# MedusaTester.net
KiCad netlist of a schematic drawn in Altium Designer
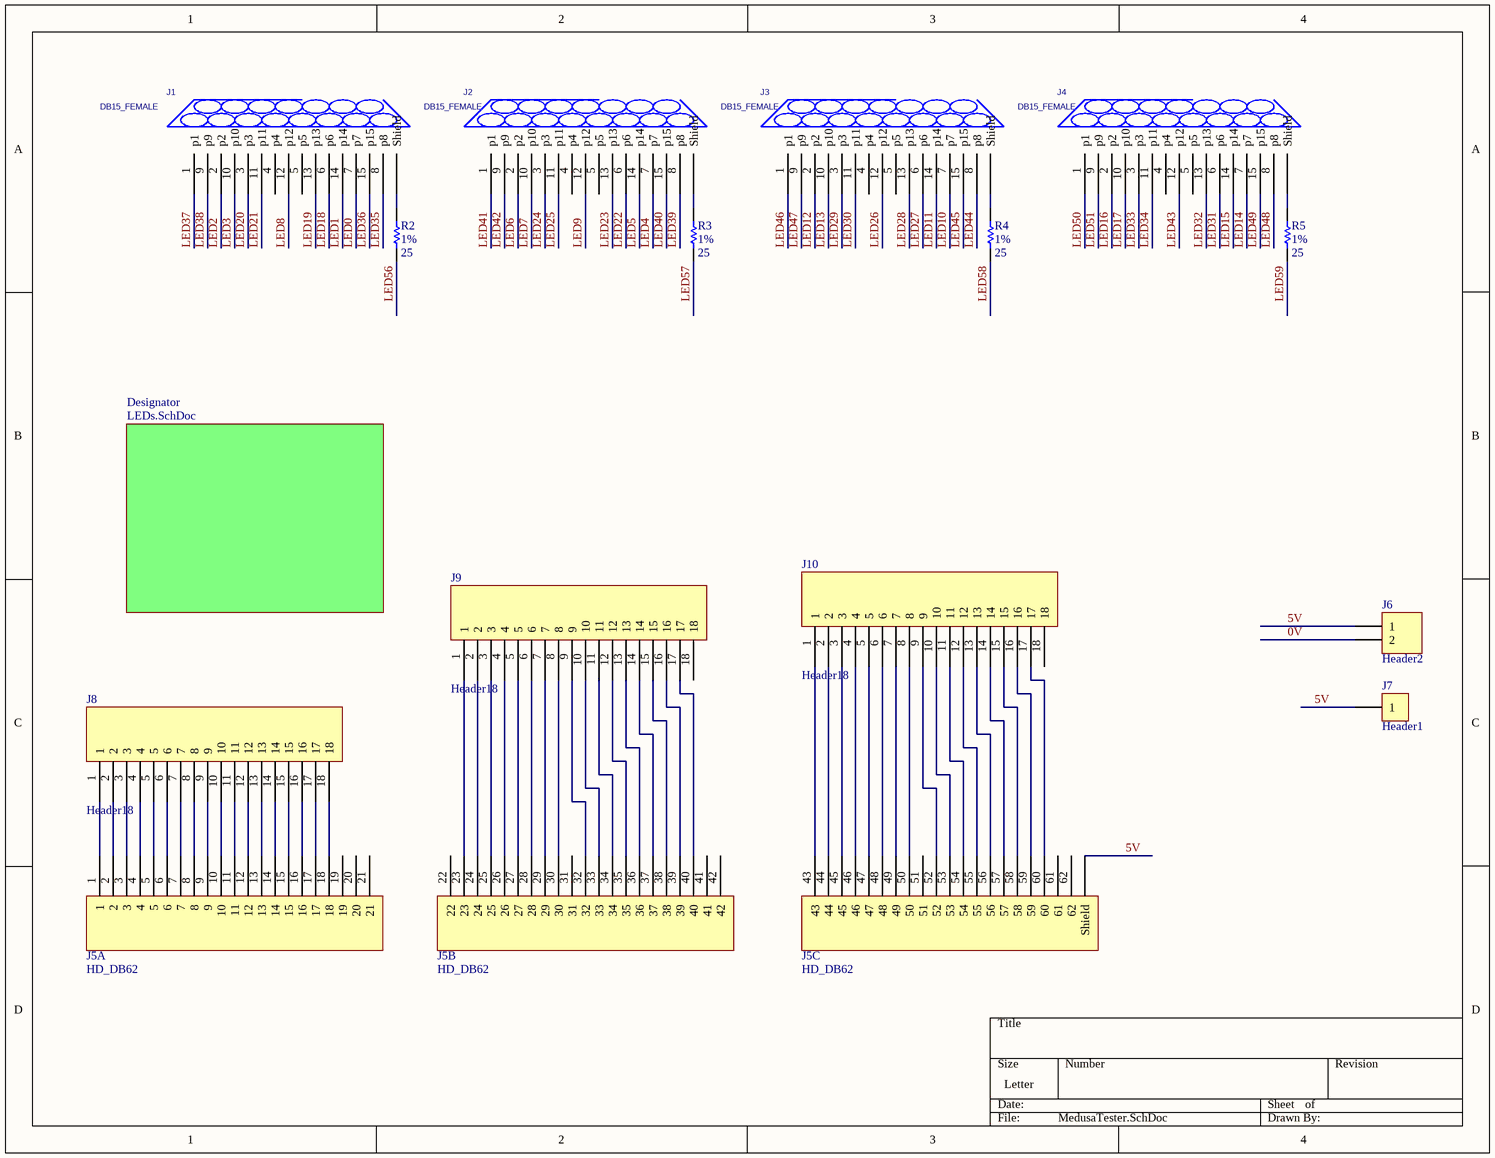
[diagram p0: MedusaTester.SchDoc]

(export (version "E")
  (design (tool "Eeschema 10.0.6"))
  (components
    (comp (ref "J1") (value "DB15_FEMALE") (libsource (lib "AdamsParts") (part "DB15_FEMALE")))
    (comp (ref "J2") (value "DB15_FEMALE") (libsource (lib "AdamsParts") (part "DB15_FEMALE")))
    (comp (ref "J3") (value "DB15_FEMALE") (libsource (lib "AdamsParts") (part "DB15_FEMALE")))
    (comp (ref "J4") (value "DB15_FEMALE") (libsource (lib "AdamsParts") (part "DB15_FEMALE")))
    (comp (ref "J5") (value "HD_DB62") (footprint "HD_DB62") (libsource (lib "AdamsParts") (part "HD_DB62")))
    (comp (ref "J6")
      (value "Header2")
      (footprint "HDR1X2")
      (libsource (lib "TEMPERATUREREADOUTSYSTEM2") (part "Header2"))
    )
    (comp (ref "J7")
      (value "Header1")
      (footprint "HDR1")
      (description "TestPoint1")
      (libsource (lib "AdamsParts") (part "Header1"))
    )
    (comp (ref "J8")
      (value "Header18")
      (footprint "HDR1X18")
      (libsource (lib "AdamsParts") (part "Header18"))
    )
    (comp (ref "J9")
      (value "Header18")
      (footprint "HDR1X18")
      (libsource (lib "AdamsParts") (part "Header18"))
    )
    (comp (ref "J10")
      (value "Header18")
      (footprint "HDR1X18")
      (libsource (lib "AdamsParts") (part "Header18"))
    )
    (comp (ref "R2")
      (value "25")
      (footprint "0603")
      (description "Resistor")
      (fields (field (name "PARAM") "1%") (field (name "Comment") "10k Ohms"))
      (libsource (lib "ClockBoard") (part "Res0603"))
    )
    (comp (ref "R3")
      (value "25")
      (footprint "0603")
      (description "Resistor")
      (fields (field (name "PARAM") "1%") (field (name "Comment") "10k Ohms"))
      (libsource (lib "ClockBoard") (part "Res0603"))
    )
    (comp (ref "R4")
      (value "25")
      (footprint "0603")
      (description "Resistor")
      (fields (field (name "PARAM") "1%") (field (name "Comment") "10k Ohms"))
      (libsource (lib "ClockBoard") (part "Res0603"))
    )
    (comp (ref "R5")
      (value "25")
      (footprint "0603")
      (description "Resistor")
      (fields (field (name "PARAM") "1%") (field (name "Comment") "10k Ohms"))
      (libsource (lib "ClockBoard") (part "Res0603"))
    )
  )
  (nets
    (net (code "1") (name "/0V") (class "Default")
      (node (ref "J6") (pin "2") (pinfunction "2_2") (pintype "passive"))
    )
    (net (code "2") (name "/5V") (class "Default")
      (node (ref "J5") (pin "HOLE63") (pinfunction "Shield_HOLE63") (pintype "passive"))
      (node (ref "J6") (pin "1") (pinfunction "1_1") (pintype "passive"))
      (node (ref "J7") (pin "1") (pinfunction "1_1") (pintype "passive"))
    )
    (net (code "3") (name "/LED0") (class "Default")
      (node (ref "J1") (pin "7") (pinfunction "p7_7") (pintype "passive"))
    )
    (net (code "4") (name "/LED1") (class "Default")
      (node (ref "J1") (pin "14") (pinfunction "p14_14") (pintype "passive"))
    )
    (net (code "5") (name "/LED2") (class "Default")
      (node (ref "J1") (pin "2") (pinfunction "p2_2") (pintype "passive"))
    )
    (net (code "6") (name "/LED3") (class "Default")
      (node (ref "J1") (pin "10") (pinfunction "p10_10") (pintype "passive"))
    )
    (net (code "7") (name "/LED4") (class "Default")
      (node (ref "J2") (pin "7") (pinfunction "p7_7") (pintype "passive"))
    )
    (net (code "8") (name "/LED5") (class "Default")
      (node (ref "J2") (pin "14") (pinfunction "p14_14") (pintype "passive"))
    )
    (net (code "9") (name "/LED6") (class "Default")
      (node (ref "J2") (pin "2") (pinfunction "p2_2") (pintype "passive"))
    )
    (net (code "10") (name "/LED7") (class "Default")
      (node (ref "J2") (pin "10") (pinfunction "p10_10") (pintype "passive"))
    )
    (net (code "11") (name "/LED8") (class "Default")
      (node (ref "J1") (pin "12") (pinfunction "p12_12") (pintype "passive"))
    )
    (net (code "12") (name "/LED9") (class "Default")
      (node (ref "J2") (pin "12") (pinfunction "p12_12") (pintype "passive"))
    )
    (net (code "13") (name "/LED10") (class "Default")
      (node (ref "J3") (pin "7") (pinfunction "p7_7") (pintype "passive"))
    )
    (net (code "14") (name "/LED11") (class "Default")
      (node (ref "J3") (pin "14") (pinfunction "p14_14") (pintype "passive"))
    )
    (net (code "15") (name "/LED12") (class "Default")
      (node (ref "J3") (pin "2") (pinfunction "p2_2") (pintype "passive"))
    )
    (net (code "16") (name "/LED13") (class "Default")
      (node (ref "J3") (pin "10") (pinfunction "p10_10") (pintype "passive"))
    )
    (net (code "17") (name "/LED14") (class "Default")
      (node (ref "J4") (pin "7") (pinfunction "p7_7") (pintype "passive"))
    )
    (net (code "18") (name "/LED15") (class "Default")
      (node (ref "J4") (pin "14") (pinfunction "p14_14") (pintype "passive"))
    )
    (net (code "19") (name "/LED16") (class "Default")
      (node (ref "J4") (pin "2") (pinfunction "p2_2") (pintype "passive"))
    )
    (net (code "20") (name "/LED17") (class "Default")
      (node (ref "J4") (pin "10") (pinfunction "p10_10") (pintype "passive"))
    )
    (net (code "21") (name "/LED18") (class "Default")
      (node (ref "J1") (pin "6") (pinfunction "p6_6") (pintype "passive"))
    )
    (net (code "22") (name "/LED19") (class "Default")
      (node (ref "J1") (pin "13") (pinfunction "p13_13") (pintype "passive"))
    )
    (net (code "23") (name "/LED20") (class "Default")
      (node (ref "J1") (pin "3") (pinfunction "p3_3") (pintype "passive"))
    )
    (net (code "24") (name "/LED21") (class "Default")
      (node (ref "J1") (pin "11") (pinfunction "p11_11") (pintype "passive"))
    )
    (net (code "25") (name "/LED22") (class "Default")
      (node (ref "J2") (pin "6") (pinfunction "p6_6") (pintype "passive"))
    )
    (net (code "26") (name "/LED23") (class "Default")
      (node (ref "J2") (pin "13") (pinfunction "p13_13") (pintype "passive"))
    )
    (net (code "27") (name "/LED24") (class "Default")
      (node (ref "J2") (pin "3") (pinfunction "p3_3") (pintype "passive"))
    )
    (net (code "28") (name "/LED25") (class "Default")
      (node (ref "J2") (pin "11") (pinfunction "p11_11") (pintype "passive"))
    )
    (net (code "29") (name "/LED26") (class "Default")
      (node (ref "J3") (pin "12") (pinfunction "p12_12") (pintype "passive"))
    )
    (net (code "30") (name "/LED27") (class "Default")
      (node (ref "J3") (pin "6") (pinfunction "p6_6") (pintype "passive"))
    )
    (net (code "31") (name "/LED28") (class "Default")
      (node (ref "J3") (pin "13") (pinfunction "p13_13") (pintype "passive"))
    )
    (net (code "32") (name "/LED29") (class "Default")
      (node (ref "J3") (pin "3") (pinfunction "p3_3") (pintype "passive"))
    )
    (net (code "33") (name "/LED30") (class "Default")
      (node (ref "J3") (pin "11") (pinfunction "p11_11") (pintype "passive"))
    )
    (net (code "34") (name "/LED31") (class "Default")
      (node (ref "J4") (pin "6") (pinfunction "p6_6") (pintype "passive"))
    )
    (net (code "35") (name "/LED32") (class "Default")
      (node (ref "J4") (pin "13") (pinfunction "p13_13") (pintype "passive"))
    )
    (net (code "36") (name "/LED33") (class "Default")
      (node (ref "J4") (pin "3") (pinfunction "p3_3") (pintype "passive"))
    )
    (net (code "37") (name "/LED34") (class "Default")
      (node (ref "J4") (pin "11") (pinfunction "p11_11") (pintype "passive"))
    )
    (net (code "38") (name "/LED35") (class "Default")
      (node (ref "J1") (pin "8") (pinfunction "p8_8") (pintype "passive"))
    )
    (net (code "39") (name "/LED36") (class "Default")
      (node (ref "J1") (pin "15") (pinfunction "p15_15") (pintype "passive"))
    )
    (net (code "40") (name "/LED37") (class "Default")
      (node (ref "J1") (pin "1") (pinfunction "p1_1") (pintype "passive"))
    )
    (net (code "41") (name "/LED38") (class "Default")
      (node (ref "J1") (pin "9") (pinfunction "p9_9") (pintype "passive"))
    )
    (net (code "42") (name "/LED39") (class "Default")
      (node (ref "J2") (pin "8") (pinfunction "p8_8") (pintype "passive"))
    )
    (net (code "43") (name "/LED40") (class "Default")
      (node (ref "J2") (pin "15") (pinfunction "p15_15") (pintype "passive"))
    )
    (net (code "44") (name "/LED41") (class "Default")
      (node (ref "J2") (pin "1") (pinfunction "p1_1") (pintype "passive"))
    )
    (net (code "45") (name "/LED42") (class "Default")
      (node (ref "J2") (pin "9") (pinfunction "p9_9") (pintype "passive"))
    )
    (net (code "46") (name "/LED43") (class "Default")
      (node (ref "J4") (pin "12") (pinfunction "p12_12") (pintype "passive"))
    )
    (net (code "47") (name "/LED44") (class "Default")
      (node (ref "J3") (pin "8") (pinfunction "p8_8") (pintype "passive"))
    )
    (net (code "48") (name "/LED45") (class "Default")
      (node (ref "J3") (pin "15") (pinfunction "p15_15") (pintype "passive"))
    )
    (net (code "49") (name "/LED46") (class "Default")
      (node (ref "J3") (pin "1") (pinfunction "p1_1") (pintype "passive"))
    )
    (net (code "50") (name "/LED47") (class "Default")
      (node (ref "J3") (pin "9") (pinfunction "p9_9") (pintype "passive"))
    )
    (net (code "51") (name "/LED48") (class "Default")
      (node (ref "J4") (pin "8") (pinfunction "p8_8") (pintype "passive"))
    )
    (net (code "52") (name "/LED49") (class "Default")
      (node (ref "J4") (pin "15") (pinfunction "p15_15") (pintype "passive"))
    )
    (net (code "53") (name "/LED50") (class "Default")
      (node (ref "J4") (pin "1") (pinfunction "p1_1") (pintype "passive"))
    )
    (net (code "54") (name "/LED51") (class "Default")
      (node (ref "J4") (pin "9") (pinfunction "p9_9") (pintype "passive"))
    )
    (net (code "55") (name "/LED56") (class "Default")
      (node (ref "R2") (pin "1") (pinfunction "1_1") (pintype "passive"))
    )
    (net (code "56") (name "/LED57") (class "Default")
      (node (ref "R3") (pin "1") (pinfunction "1_1") (pintype "passive"))
    )
    (net (code "57") (name "/LED58") (class "Default")
      (node (ref "R4") (pin "1") (pinfunction "1_1") (pintype "passive"))
    )
    (net (code "58") (name "/LED59") (class "Default")
      (node (ref "R5") (pin "1") (pinfunction "1_1") (pintype "passive"))
    )
    (net (code "59") (name "Net-(J1-Shield)") (class "Default")
      (node (ref "J1") (pin "Hole30") (pinfunction "Shield_Hole30") (pintype "passive"))
      (node (ref "R2") (pin "2") (pinfunction "2_2") (pintype "passive"))
    )
    (net (code "60") (name "Net-(J2-Shield)") (class "Default")
      (node (ref "J2") (pin "Hole30") (pinfunction "Shield_Hole30") (pintype "passive"))
      (node (ref "R3") (pin "2") (pinfunction "2_2") (pintype "passive"))
    )
    (net (code "61") (name "Net-(J3-Shield)") (class "Default")
      (node (ref "J3") (pin "Hole30") (pinfunction "Shield_Hole30") (pintype "passive"))
      (node (ref "R4") (pin "2") (pinfunction "2_2") (pintype "passive"))
    )
    (net (code "62") (name "Net-(J4-Shield)") (class "Default")
      (node (ref "J4") (pin "Hole30") (pinfunction "Shield_Hole30") (pintype "passive"))
      (node (ref "R5") (pin "2") (pinfunction "2_2") (pintype "passive"))
    )
    (net (code "63") (name "Net-(J5-Pad1)") (class "Default")
      (node (ref "J5") (pin "1") (pinfunction "1_1") (pintype "passive"))
      (node (ref "J8") (pin "1") (pinfunction "1_1") (pintype "passive"))
    )
    (net (code "64") (name "Net-(J5-Pad2)") (class "Default")
      (node (ref "J5") (pin "2") (pinfunction "2_2") (pintype "passive"))
      (node (ref "J8") (pin "2") (pinfunction "2_2") (pintype "passive"))
    )
    (net (code "65") (name "Net-(J5-Pad3)") (class "Default")
      (node (ref "J5") (pin "3") (pinfunction "3_3") (pintype "passive"))
      (node (ref "J8") (pin "3") (pinfunction "3_3") (pintype "passive"))
    )
    (net (code "66") (name "Net-(J5-Pad4)") (class "Default")
      (node (ref "J5") (pin "4") (pinfunction "4_4") (pintype "passive"))
      (node (ref "J8") (pin "4") (pinfunction "4_4") (pintype "passive"))
    )
    (net (code "67") (name "Net-(J5-Pad5)") (class "Default")
      (node (ref "J5") (pin "5") (pinfunction "5_5") (pintype "passive"))
      (node (ref "J8") (pin "5") (pinfunction "5_5") (pintype "passive"))
    )
    (net (code "68") (name "Net-(J5-Pad6)") (class "Default")
      (node (ref "J5") (pin "6") (pinfunction "6_6") (pintype "passive"))
      (node (ref "J8") (pin "6") (pinfunction "6_6") (pintype "passive"))
    )
    (net (code "69") (name "Net-(J5-Pad7)") (class "Default")
      (node (ref "J5") (pin "7") (pinfunction "7_7") (pintype "passive"))
      (node (ref "J8") (pin "7") (pinfunction "7_7") (pintype "passive"))
    )
    (net (code "70") (name "Net-(J5-Pad8)") (class "Default")
      (node (ref "J5") (pin "8") (pinfunction "8_8") (pintype "passive"))
      (node (ref "J8") (pin "8") (pinfunction "8_8") (pintype "passive"))
    )
    (net (code "71") (name "Net-(J5-Pad9)") (class "Default")
      (node (ref "J5") (pin "9") (pinfunction "9_9") (pintype "passive"))
      (node (ref "J8") (pin "9") (pinfunction "9_9") (pintype "passive"))
    )
    (net (code "72") (name "Net-(J5-Pad10)") (class "Default")
      (node (ref "J5") (pin "10") (pinfunction "10_10") (pintype "passive"))
      (node (ref "J8") (pin "10") (pinfunction "10_10") (pintype "passive"))
    )
    (net (code "73") (name "Net-(J5-Pad11)") (class "Default")
      (node (ref "J5") (pin "11") (pinfunction "11_11") (pintype "passive"))
      (node (ref "J8") (pin "11") (pinfunction "11_11") (pintype "passive"))
    )
    (net (code "74") (name "Net-(J5-Pad12)") (class "Default")
      (node (ref "J5") (pin "12") (pinfunction "12_12") (pintype "passive"))
      (node (ref "J8") (pin "12") (pinfunction "12_12") (pintype "passive"))
    )
    (net (code "75") (name "Net-(J5-Pad13)") (class "Default")
      (node (ref "J5") (pin "13") (pinfunction "13_13") (pintype "passive"))
      (node (ref "J8") (pin "13") (pinfunction "13_13") (pintype "passive"))
    )
    (net (code "76") (name "Net-(J5-Pad14)") (class "Default")
      (node (ref "J5") (pin "14") (pinfunction "14_14") (pintype "passive"))
      (node (ref "J8") (pin "14") (pinfunction "14_14") (pintype "passive"))
    )
    (net (code "77") (name "Net-(J5-Pad15)") (class "Default")
      (node (ref "J5") (pin "15") (pinfunction "15_15") (pintype "passive"))
      (node (ref "J8") (pin "15") (pinfunction "15_15") (pintype "passive"))
    )
    (net (code "78") (name "Net-(J5-Pad16)") (class "Default")
      (node (ref "J5") (pin "16") (pinfunction "16_16") (pintype "passive"))
      (node (ref "J8") (pin "16") (pinfunction "16_16") (pintype "passive"))
    )
    (net (code "79") (name "Net-(J5-Pad17)") (class "Default")
      (node (ref "J5") (pin "17") (pinfunction "17_17") (pintype "passive"))
      (node (ref "J8") (pin "17") (pinfunction "17_17") (pintype "passive"))
    )
    (net (code "80") (name "Net-(J5-Pad18)") (class "Default")
      (node (ref "J5") (pin "18") (pinfunction "18_18") (pintype "passive"))
      (node (ref "J8") (pin "18") (pinfunction "18_18") (pintype "passive"))
    )
    (net (code "81") (name "Net-(J5-Pad23)") (class "Default")
      (node (ref "J5") (pin "23") (pinfunction "23_23") (pintype "passive"))
      (node (ref "J9") (pin "1") (pinfunction "1_1") (pintype "passive"))
    )
    (net (code "82") (name "Net-(J5-Pad24)") (class "Default")
      (node (ref "J5") (pin "24") (pinfunction "24_24") (pintype "passive"))
      (node (ref "J9") (pin "2") (pinfunction "2_2") (pintype "passive"))
    )
    (net (code "83") (name "Net-(J5-Pad25)") (class "Default")
      (node (ref "J5") (pin "25") (pinfunction "25_25") (pintype "passive"))
      (node (ref "J9") (pin "3") (pinfunction "3_3") (pintype "passive"))
    )
    (net (code "84") (name "Net-(J5-Pad26)") (class "Default")
      (node (ref "J5") (pin "26") (pinfunction "26_26") (pintype "passive"))
      (node (ref "J9") (pin "4") (pinfunction "4_4") (pintype "passive"))
    )
    (net (code "85") (name "Net-(J5-Pad27)") (class "Default")
      (node (ref "J5") (pin "27") (pinfunction "27_27") (pintype "passive"))
      (node (ref "J9") (pin "5") (pinfunction "5_5") (pintype "passive"))
    )
    (net (code "86") (name "Net-(J5-Pad28)") (class "Default")
      (node (ref "J5") (pin "28") (pinfunction "28_28") (pintype "passive"))
      (node (ref "J9") (pin "6") (pinfunction "6_6") (pintype "passive"))
    )
    (net (code "87") (name "Net-(J5-Pad29)") (class "Default")
      (node (ref "J5") (pin "29") (pinfunction "29_29") (pintype "passive"))
      (node (ref "J9") (pin "7") (pinfunction "7_7") (pintype "passive"))
    )
    (net (code "88") (name "Net-(J5-Pad30)") (class "Default")
      (node (ref "J5") (pin "30") (pinfunction "30_30") (pintype "passive"))
      (node (ref "J9") (pin "8") (pinfunction "8_8") (pintype "passive"))
    )
    (net (code "89") (name "Net-(J5-Pad32)") (class "Default")
      (node (ref "J5") (pin "32") (pinfunction "32_32") (pintype "passive"))
      (node (ref "J9") (pin "9") (pinfunction "9_9") (pintype "passive"))
    )
    (net (code "90") (name "Net-(J5-Pad33)") (class "Default")
      (node (ref "J5") (pin "33") (pinfunction "33_33") (pintype "passive"))
      (node (ref "J9") (pin "10") (pinfunction "10_10") (pintype "passive"))
    )
    (net (code "91") (name "Net-(J5-Pad34)") (class "Default")
      (node (ref "J5") (pin "34") (pinfunction "34_34") (pintype "passive"))
      (node (ref "J9") (pin "11") (pinfunction "11_11") (pintype "passive"))
    )
    (net (code "92") (name "Net-(J5-Pad35)") (class "Default")
      (node (ref "J5") (pin "35") (pinfunction "35_35") (pintype "passive"))
      (node (ref "J9") (pin "12") (pinfunction "12_12") (pintype "passive"))
    )
    (net (code "93") (name "Net-(J5-Pad36)") (class "Default")
      (node (ref "J5") (pin "36") (pinfunction "36_36") (pintype "passive"))
      (node (ref "J9") (pin "13") (pinfunction "13_13") (pintype "passive"))
    )
    (net (code "94") (name "Net-(J5-Pad37)") (class "Default")
      (node (ref "J5") (pin "37") (pinfunction "37_37") (pintype "passive"))
      (node (ref "J9") (pin "14") (pinfunction "14_14") (pintype "passive"))
    )
    (net (code "95") (name "Net-(J5-Pad38)") (class "Default")
      (node (ref "J5") (pin "38") (pinfunction "38_38") (pintype "passive"))
      (node (ref "J9") (pin "15") (pinfunction "15_15") (pintype "passive"))
    )
    (net (code "96") (name "Net-(J5-Pad39)") (class "Default")
      (node (ref "J5") (pin "39") (pinfunction "39_39") (pintype "passive"))
      (node (ref "J9") (pin "16") (pinfunction "16_16") (pintype "passive"))
    )
    (net (code "97") (name "Net-(J5-Pad40)") (class "Default")
      (node (ref "J5") (pin "40") (pinfunction "40_40") (pintype "passive"))
      (node (ref "J9") (pin "17") (pinfunction "17_17") (pintype "passive"))
    )
    (net (code "98") (name "Net-(J10-Pad1)") (class "Default")
      (node (ref "J10") (pin "1") (pinfunction "1_1") (pintype "passive"))
      (node (ref "J5") (pin "43") (pinfunction "43_43") (pintype "passive"))
    )
    (net (code "99") (name "Net-(J10-Pad2)") (class "Default")
      (node (ref "J10") (pin "2") (pinfunction "2_2") (pintype "passive"))
      (node (ref "J5") (pin "44") (pinfunction "44_44") (pintype "passive"))
    )
    (net (code "100") (name "Net-(J10-Pad3)") (class "Default")
      (node (ref "J10") (pin "3") (pinfunction "3_3") (pintype "passive"))
      (node (ref "J5") (pin "45") (pinfunction "45_45") (pintype "passive"))
    )
    (net (code "101") (name "Net-(J10-Pad4)") (class "Default")
      (node (ref "J10") (pin "4") (pinfunction "4_4") (pintype "passive"))
      (node (ref "J5") (pin "46") (pinfunction "46_46") (pintype "passive"))
    )
    (net (code "102") (name "Net-(J10-Pad5)") (class "Default")
      (node (ref "J10") (pin "5") (pinfunction "5_5") (pintype "passive"))
      (node (ref "J5") (pin "47") (pinfunction "47_47") (pintype "passive"))
    )
    (net (code "103") (name "Net-(J10-Pad6)") (class "Default")
      (node (ref "J10") (pin "6") (pinfunction "6_6") (pintype "passive"))
      (node (ref "J5") (pin "48") (pinfunction "48_48") (pintype "passive"))
    )
    (net (code "104") (name "Net-(J10-Pad7)") (class "Default")
      (node (ref "J10") (pin "7") (pinfunction "7_7") (pintype "passive"))
      (node (ref "J5") (pin "49") (pinfunction "49_49") (pintype "passive"))
    )
    (net (code "105") (name "Net-(J10-Pad8)") (class "Default")
      (node (ref "J10") (pin "8") (pinfunction "8_8") (pintype "passive"))
      (node (ref "J5") (pin "50") (pinfunction "50_50") (pintype "passive"))
    )
    (net (code "106") (name "Net-(J10-Pad9)") (class "Default")
      (node (ref "J10") (pin "9") (pinfunction "9_9") (pintype "passive"))
      (node (ref "J5") (pin "52") (pinfunction "52_52") (pintype "passive"))
    )
    (net (code "107") (name "Net-(J10-Pad10)") (class "Default")
      (node (ref "J10") (pin "10") (pinfunction "10_10") (pintype "passive"))
      (node (ref "J5") (pin "53") (pinfunction "53_53") (pintype "passive"))
    )
    (net (code "108") (name "Net-(J10-Pad11)") (class "Default")
      (node (ref "J10") (pin "11") (pinfunction "11_11") (pintype "passive"))
      (node (ref "J5") (pin "54") (pinfunction "54_54") (pintype "passive"))
    )
    (net (code "109") (name "Net-(J10-Pad12)") (class "Default")
      (node (ref "J10") (pin "12") (pinfunction "12_12") (pintype "passive"))
      (node (ref "J5") (pin "55") (pinfunction "55_55") (pintype "passive"))
    )
    (net (code "110") (name "Net-(J10-Pad13)") (class "Default")
      (node (ref "J10") (pin "13") (pinfunction "13_13") (pintype "passive"))
      (node (ref "J5") (pin "56") (pinfunction "56_56") (pintype "passive"))
    )
    (net (code "111") (name "Net-(J10-Pad14)") (class "Default")
      (node (ref "J10") (pin "14") (pinfunction "14_14") (pintype "passive"))
      (node (ref "J5") (pin "57") (pinfunction "57_57") (pintype "passive"))
    )
    (net (code "112") (name "Net-(J10-Pad15)") (class "Default")
      (node (ref "J10") (pin "15") (pinfunction "15_15") (pintype "passive"))
      (node (ref "J5") (pin "58") (pinfunction "58_58") (pintype "passive"))
    )
    (net (code "113") (name "Net-(J10-Pad16)") (class "Default")
      (node (ref "J10") (pin "16") (pinfunction "16_16") (pintype "passive"))
      (node (ref "J5") (pin "59") (pinfunction "59_59") (pintype "passive"))
    )
    (net (code "114") (name "Net-(J10-Pad17)") (class "Default")
      (node (ref "J10") (pin "17") (pinfunction "17_17") (pintype "passive"))
      (node (ref "J5") (pin "60") (pinfunction "60_60") (pintype "passive"))
    )
    (net (code "115") (name "unconnected-(J1-p4-Pad4)") (class "Default")
      (node (ref "J1") (pin "4") (pinfunction "p4_4") (pintype "passive"))
    )
    (net (code "116") (name "unconnected-(J1-p5-Pad5)") (class "Default")
      (node (ref "J1") (pin "5") (pinfunction "p5_5") (pintype "passive"))
    )
    (net (code "117") (name "unconnected-(J2-p4-Pad4)") (class "Default")
      (node (ref "J2") (pin "4") (pinfunction "p4_4") (pintype "passive"))
    )
    (net (code "118") (name "unconnected-(J2-p5-Pad5)") (class "Default")
      (node (ref "J2") (pin "5") (pinfunction "p5_5") (pintype "passive"))
    )
    (net (code "119") (name "unconnected-(J3-p4-Pad4)") (class "Default")
      (node (ref "J3") (pin "4") (pinfunction "p4_4") (pintype "passive"))
    )
    (net (code "120") (name "unconnected-(J3-p5-Pad5)") (class "Default")
      (node (ref "J3") (pin "5") (pinfunction "p5_5") (pintype "passive"))
    )
    (net (code "121") (name "unconnected-(J4-p4-Pad4)") (class "Default")
      (node (ref "J4") (pin "4") (pinfunction "p4_4") (pintype "passive"))
    )
    (net (code "122") (name "unconnected-(J4-p5-Pad5)") (class "Default")
      (node (ref "J4") (pin "5") (pinfunction "p5_5") (pintype "passive"))
    )
    (net (code "123") (name "unconnected-(J5-Pad19)") (class "Default")
      (node (ref "J5") (pin "19") (pinfunction "19_19") (pintype "passive"))
    )
    (net (code "124") (name "unconnected-(J5-Pad20)") (class "Default")
      (node (ref "J5") (pin "20") (pinfunction "20_20") (pintype "passive"))
    )
    (net (code "125") (name "unconnected-(J5-Pad21)") (class "Default")
      (node (ref "J5") (pin "21") (pinfunction "21_21") (pintype "passive"))
    )
    (net (code "126") (name "unconnected-(J5-Pad22)") (class "Default")
      (node (ref "J5") (pin "22") (pinfunction "22_22") (pintype "passive"))
    )
    (net (code "127") (name "unconnected-(J5-Pad31)") (class "Default")
      (node (ref "J5") (pin "31") (pinfunction "31_31") (pintype "passive"))
    )
    (net (code "128") (name "unconnected-(J5-Pad41)") (class "Default")
      (node (ref "J5") (pin "41") (pinfunction "41_41") (pintype "passive"))
    )
    (net (code "129") (name "unconnected-(J5-Pad42)") (class "Default")
      (node (ref "J5") (pin "42") (pinfunction "42_42") (pintype "passive"))
    )
    (net (code "130") (name "unconnected-(J5-Pad51)") (class "Default")
      (node (ref "J5") (pin "51") (pinfunction "51_51") (pintype "passive"))
    )
    (net (code "131") (name "unconnected-(J5-Pad61)") (class "Default")
      (node (ref "J5") (pin "61") (pinfunction "61_61") (pintype "passive"))
    )
    (net (code "132") (name "unconnected-(J5-Pad62)") (class "Default")
      (node (ref "J5") (pin "62") (pinfunction "62_62") (pintype "passive"))
    )
    (net (code "133") (name "unconnected-(J9-Pad18)") (class "Default")
      (node (ref "J9") (pin "18") (pinfunction "18_18") (pintype "passive"))
    )
    (net (code "134") (name "unconnected-(J10-Pad18)") (class "Default")
      (node (ref "J10") (pin "18") (pinfunction "18_18") (pintype "passive"))
    )
  )
)
